# microsd-switch.net
KiCad netlist of a schematic drawn in EAGLE
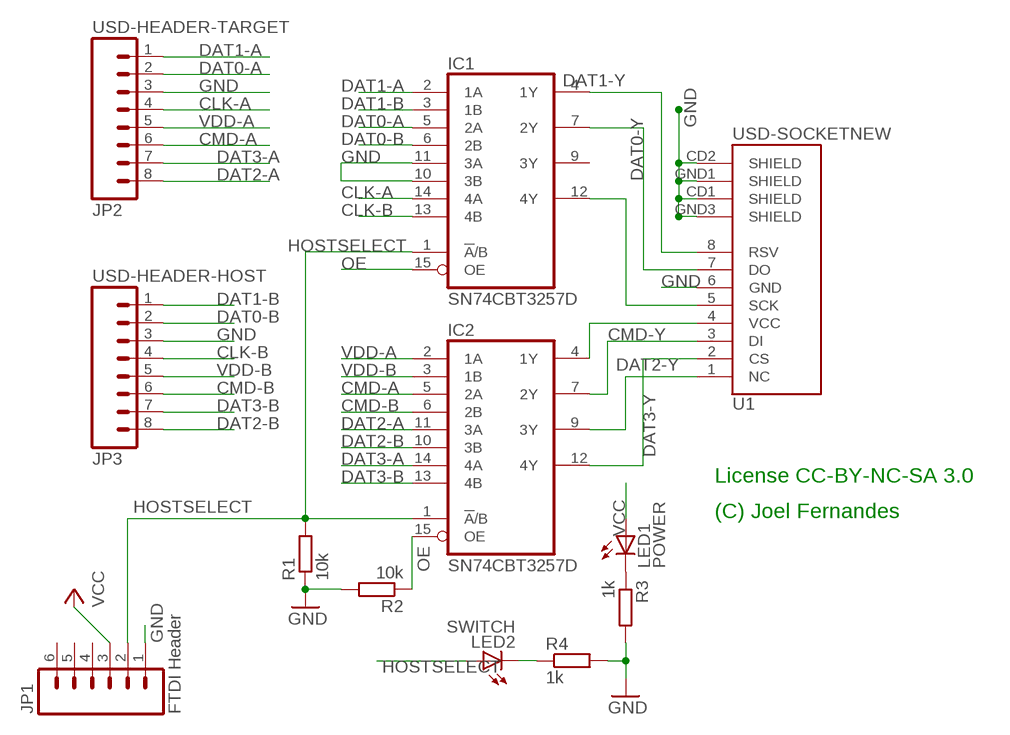
[diagram p0: schematic, sheet 1]

(export (version "E")
  (design (tool "Eeschema 10.0.6"))
  (components
    (comp (ref "IC1")
      (value "SN74CBT3257D")
      (footprint "eagle-import:SO16")
      (libsource (lib "eagle-import") (part "SN74CBT3257D"))
    )
    (comp (ref "IC2")
      (value "SN74CBT3257D")
      (footprint "eagle-import:SO16")
      (libsource (lib "eagle-import") (part "SN74CBT3257D"))
    )
    (comp (ref "JP1")
      (value "FTDI Header")
      (footprint "eagle-import:1X06_LOCK")
      (libsource (lib "eagle-import") (part "M06LOCK"))
    )
    (comp (ref "JP2")
      (value "USD-HEADER-TARGET")
      (footprint "eagle-import:1X08_LOCK")
      (libsource (lib "eagle-import") (part "M08LOCK"))
    )
    (comp (ref "JP3")
      (value "USD-HEADER-HOST")
      (footprint "eagle-import:1X08_LOCK")
      (libsource (lib "eagle-import") (part "M08LOCK"))
    )
    (comp (ref "LED1")
      (value "POWER")
      (footprint "eagle-import:CHIP-LED0805")
      (libsource (lib "eagle-import") (part "LEDCHIP-LED0805"))
    )
    (comp (ref "LED2")
      (value "SWITCH")
      (footprint "eagle-import:CHIP-LED0805")
      (libsource (lib "eagle-import") (part "LEDCHIP-LED0805"))
    )
    (comp (ref "R1")
      (value "10k")
      (footprint "eagle-import:R1206")
      (libsource (lib "eagle-import") (part "R-EU_R1206"))
    )
    (comp (ref "R2")
      (value "10k")
      (footprint "eagle-import:R1206")
      (libsource (lib "eagle-import") (part "R-EU_R1206"))
    )
    (comp (ref "R3")
      (value "1k")
      (footprint "eagle-import:R1206")
      (libsource (lib "eagle-import") (part "R-EU_R1206"))
    )
    (comp (ref "R4")
      (value "1k")
      (footprint "eagle-import:R1206")
      (libsource (lib "eagle-import") (part "R-EU_R1206"))
    )
    (comp (ref "U1")
      (value "USD-SOCKETNEW")
      (footprint "eagle-import:MICRO-SD-SOCKET-PP")
      (libsource (lib "eagle-import") (part "USD-SOCKETNEW"))
    )
  )
  (nets
    (net (code "1") (name "/CLK-A") (class "Default")
      (node (ref "IC1") (pin "14") (pinfunction "4A_14") (pintype "input"))
      (node (ref "JP2") (pin "4") (pinfunction "4_4") (pintype "passive"))
    )
    (net (code "2") (name "/CLK-B") (class "Default")
      (node (ref "IC1") (pin "13") (pinfunction "4B_13") (pintype "input"))
      (node (ref "JP3") (pin "4") (pinfunction "4_4") (pintype "passive"))
    )
    (net (code "3") (name "/CMD-A") (class "Default")
      (node (ref "IC2") (pin "5") (pinfunction "2A_5") (pintype "input"))
      (node (ref "JP2") (pin "6") (pinfunction "6_6") (pintype "passive"))
    )
    (net (code "4") (name "/CMD-B") (class "Default")
      (node (ref "IC2") (pin "6") (pinfunction "2B_6") (pintype "input"))
      (node (ref "JP3") (pin "6") (pinfunction "6_6") (pintype "passive"))
    )
    (net (code "5") (name "/CMD-Y") (class "Default")
      (node (ref "IC2") (pin "7") (pinfunction "2Y_7") (pintype "output"))
      (node (ref "U1") (pin "3") (pinfunction "DI_3") (pintype "bidirectional"))
    )
    (net (code "6") (name "/DAT0-A") (class "Default")
      (node (ref "IC1") (pin "5") (pinfunction "2A_5") (pintype "input"))
      (node (ref "JP2") (pin "2") (pinfunction "2_2") (pintype "passive"))
    )
    (net (code "7") (name "/DAT0-B") (class "Default")
      (node (ref "IC1") (pin "6") (pinfunction "2B_6") (pintype "input"))
      (node (ref "JP3") (pin "2") (pinfunction "2_2") (pintype "passive"))
    )
    (net (code "8") (name "/DAT0-Y") (class "Default")
      (node (ref "IC1") (pin "7") (pinfunction "2Y_7") (pintype "output"))
      (node (ref "U1") (pin "7") (pinfunction "DO_7") (pintype "bidirectional"))
    )
    (net (code "9") (name "/DAT1-A") (class "Default")
      (node (ref "IC1") (pin "2") (pinfunction "1A_2") (pintype "input"))
      (node (ref "JP2") (pin "1") (pinfunction "1_1") (pintype "passive"))
    )
    (net (code "10") (name "/DAT1-B") (class "Default")
      (node (ref "IC1") (pin "3") (pinfunction "1B_3") (pintype "input"))
      (node (ref "JP3") (pin "1") (pinfunction "1_1") (pintype "passive"))
    )
    (net (code "11") (name "/DAT1-Y") (class "Default")
      (node (ref "IC1") (pin "4") (pinfunction "1Y_4") (pintype "output"))
      (node (ref "U1") (pin "8") (pinfunction "RSV_8") (pintype "bidirectional"))
    )
    (net (code "12") (name "/DAT2-A") (class "Default")
      (node (ref "IC2") (pin "11") (pinfunction "3A_11") (pintype "input"))
      (node (ref "JP2") (pin "8") (pinfunction "8_8") (pintype "passive"))
    )
    (net (code "13") (name "/DAT2-B") (class "Default")
      (node (ref "IC2") (pin "10") (pinfunction "3B_10") (pintype "input"))
      (node (ref "JP3") (pin "8") (pinfunction "8_8") (pintype "passive"))
    )
    (net (code "14") (name "/DAT2-Y") (class "Default")
      (node (ref "IC2") (pin "9") (pinfunction "3Y_9") (pintype "output"))
      (node (ref "U1") (pin "1") (pinfunction "NC_1") (pintype "bidirectional"))
    )
    (net (code "15") (name "/DAT3-A") (class "Default")
      (node (ref "IC2") (pin "14") (pinfunction "4A_14") (pintype "input"))
      (node (ref "JP2") (pin "7") (pinfunction "7_7") (pintype "passive"))
    )
    (net (code "16") (name "/DAT3-B") (class "Default")
      (node (ref "IC2") (pin "13") (pinfunction "4B_13") (pintype "input"))
      (node (ref "JP3") (pin "7") (pinfunction "7_7") (pintype "passive"))
    )
    (net (code "17") (name "/DAT3-Y") (class "Default")
      (node (ref "IC2") (pin "12") (pinfunction "4Y_12") (pintype "output"))
      (node (ref "U1") (pin "2") (pinfunction "CS_2") (pintype "bidirectional"))
    )
    (net (code "18") (name "/HOSTSELECT") (class "Default")
      (node (ref "IC1") (pin "1") (pinfunction "~{A}/B_1") (pintype "input"))
      (node (ref "IC2") (pin "1") (pinfunction "~{A}/B_1") (pintype "input"))
      (node (ref "JP1") (pin "2") (pinfunction "2_2") (pintype "passive"))
      (node (ref "LED2") (pin "A") (pinfunction "A_A") (pintype "passive"))
      (node (ref "R1") (pin "2") (pinfunction "2_2") (pintype "passive"))
    )
    (net (code "19") (name "/OE") (class "Default")
      (node (ref "IC1") (pin "15") (pinfunction "OE_15") (pintype "input"))
      (node (ref "IC2") (pin "15") (pinfunction "OE_15") (pintype "input"))
      (node (ref "R2") (pin "1") (pinfunction "1_1") (pintype "passive"))
    )
    (net (code "20") (name "/VDD-A") (class "Default")
      (node (ref "IC2") (pin "2") (pinfunction "1A_2") (pintype "input"))
      (node (ref "JP2") (pin "5") (pinfunction "5_5") (pintype "passive"))
    )
    (net (code "21") (name "/VDD-B") (class "Default")
      (node (ref "IC2") (pin "3") (pinfunction "1B_3") (pintype "input"))
      (node (ref "JP3") (pin "5") (pinfunction "5_5") (pintype "passive"))
    )
    (net (code "22") (name "GND") (class "Default")
      (node (ref "IC1") (pin "10") (pinfunction "3B_10") (pintype "input"))
      (node (ref "IC1") (pin "11") (pinfunction "3A_11") (pintype "input"))
      (node (ref "JP1") (pin "1") (pinfunction "1_1") (pintype "passive"))
      (node (ref "JP2") (pin "3") (pinfunction "3_3") (pintype "passive"))
      (node (ref "JP3") (pin "3") (pinfunction "3_3") (pintype "passive"))
      (node (ref "R1") (pin "1") (pinfunction "1_1") (pintype "passive"))
      (node (ref "R2") (pin "2") (pinfunction "2_2") (pintype "passive"))
      (node (ref "R3") (pin "2") (pinfunction "2_2") (pintype "passive"))
      (node (ref "R4") (pin "2") (pinfunction "2_2") (pintype "passive"))
      (node (ref "U1") (pin "6") (pinfunction "GND_6") (pintype "bidirectional"))
      (node (ref "U1") (pin "CD1") (pinfunction "SHIELD_CD1") (pintype "bidirectional"))
      (node (ref "U1") (pin "CD2") (pinfunction "SHIELD_CD2") (pintype "bidirectional"))
      (node (ref "U1") (pin "GND1") (pinfunction "SHIELD_GND1") (pintype "bidirectional"))
      (node (ref "U1") (pin "GND3") (pinfunction "SHIELD_GND3") (pintype "bidirectional"))
    )
    (net (code "23") (name "Net-(IC1A-4Y)") (class "Default")
      (node (ref "IC1") (pin "12") (pinfunction "4Y_12") (pintype "output"))
      (node (ref "U1") (pin "5") (pinfunction "SCK_5") (pintype "bidirectional"))
    )
    (net (code "24") (name "Net-(IC2A-1Y)") (class "Default")
      (node (ref "IC2") (pin "4") (pinfunction "1Y_4") (pintype "output"))
      (node (ref "U1") (pin "4") (pinfunction "VCC_4") (pintype "bidirectional"))
    )
    (net (code "25") (name "Net-(LED1-PadC)") (class "Default")
      (node (ref "LED1") (pin "C") (pinfunction "C_C") (pintype "passive"))
      (node (ref "R3") (pin "1") (pinfunction "1_1") (pintype "passive"))
    )
    (net (code "26") (name "Net-(LED2-PadC)") (class "Default")
      (node (ref "LED2") (pin "C") (pinfunction "C_C") (pintype "passive"))
      (node (ref "R4") (pin "1") (pinfunction "1_1") (pintype "passive"))
    )
    (net (code "27") (name "VCC") (class "Default")
      (node (ref "JP1") (pin "3") (pinfunction "3_3") (pintype "passive"))
      (node (ref "LED1") (pin "A") (pinfunction "A_A") (pintype "passive"))
    )
    (net (code "28") (name "unconnected-(IC1A-3Y-Pad9)") (class "Default")
      (node (ref "IC1") (pin "9") (pinfunction "3Y_9") (pintype "output"))
    )
    (net (code "29") (name "unconnected-(JP1-Pad4)") (class "Default")
      (node (ref "JP1") (pin "4") (pinfunction "4_4") (pintype "passive"))
    )
    (net (code "30") (name "unconnected-(JP1-Pad5)") (class "Default")
      (node (ref "JP1") (pin "5") (pinfunction "5_5") (pintype "passive"))
    )
    (net (code "31") (name "unconnected-(JP1-Pad6)") (class "Default")
      (node (ref "JP1") (pin "6") (pinfunction "6_6") (pintype "passive"))
    )
  )
)
